# MiniRover.net
KiCad netlist of a schematic drawn in Altium Designer
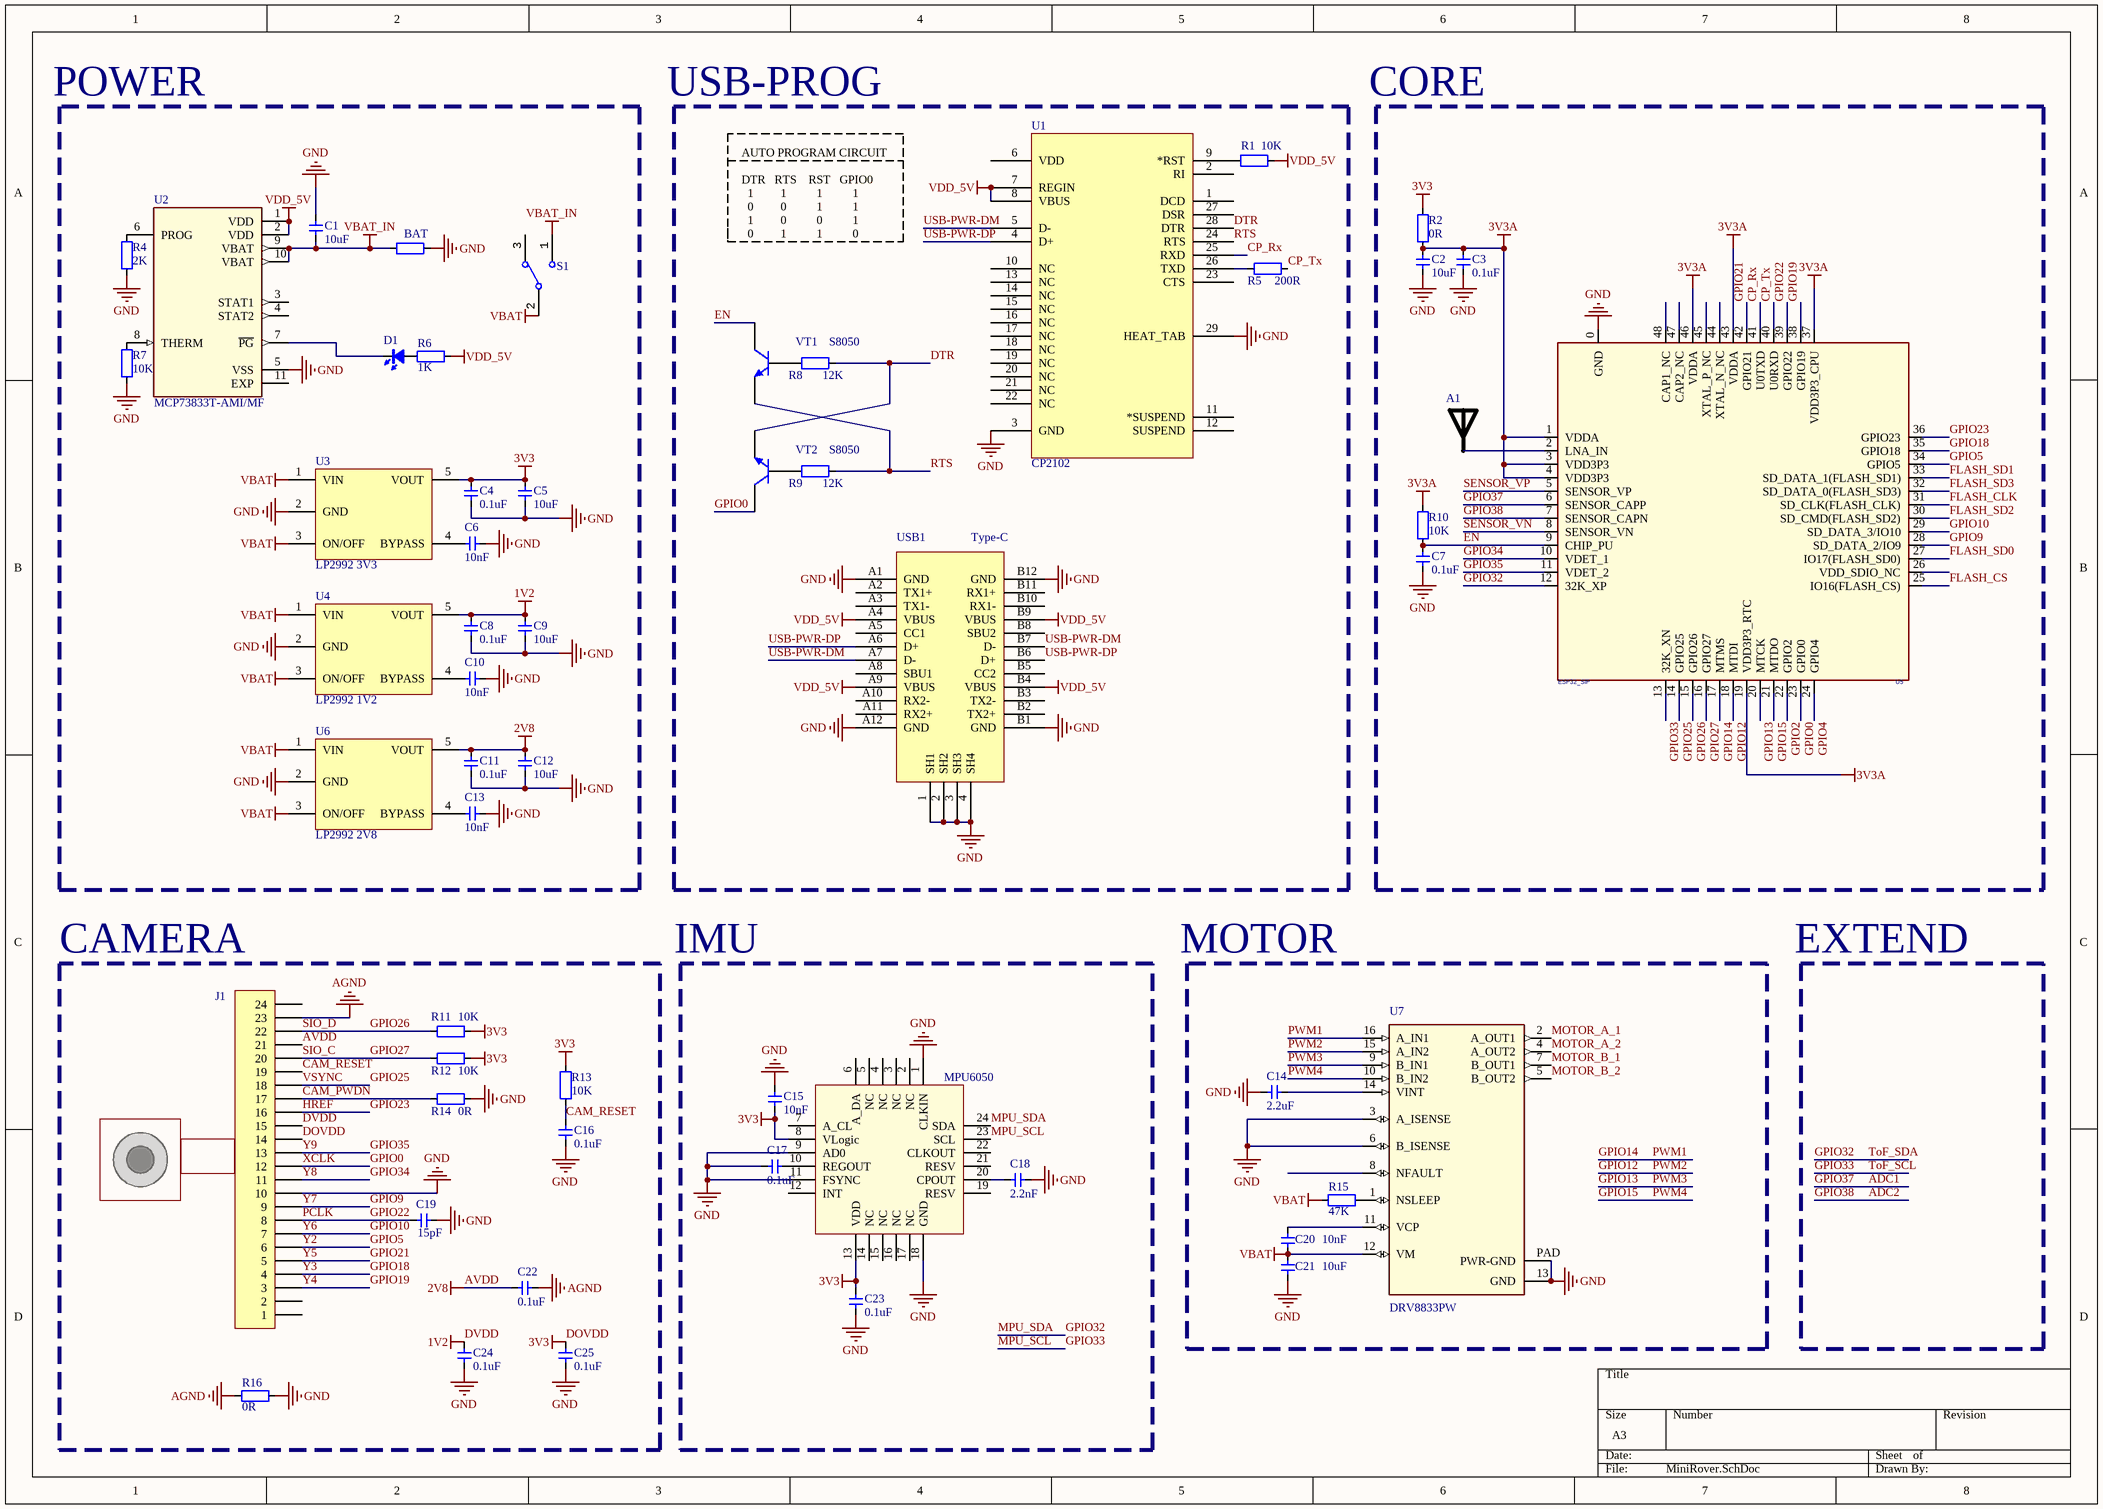
[diagram p0: MiniRover.SchDoc]

(export (version "E")
  (design (tool "Eeschema 10.0.6"))
  (components
    (comp (ref "A1")
      (value "RAINSUN")
      (footprint "ANT-Rainsun-AN5120")
      (libsource (lib "MyPcbLib") (part "ANT-Rainsun-AP5120"))
    )
    (comp (ref "C1")
      (value "10uF")
      (footprint "0603-CAP")
      (description "Capacitor")
      (libsource (lib "MyPcbLib") (part "电容-0603"))
    )
    (comp (ref "C2")
      (value "10uF")
      (footprint "0603-CAP")
      (description "Capacitor")
      (libsource (lib "MyPcbLib") (part "电容-0603"))
    )
    (comp (ref "C3")
      (value "0.1uF")
      (footprint "CAP_0402")
      (description "Capacitor")
      (libsource (lib "MyPcbLib") (part "电容-0402"))
    )
    (comp (ref "C4")
      (value "0.1uF")
      (footprint "CAP_0402")
      (description "Capacitor")
      (libsource (lib "MyPcbLib") (part "电容-0402"))
    )
    (comp (ref "C5")
      (value "10uF")
      (footprint "0603-CAP")
      (description "Capacitor")
      (libsource (lib "MyPcbLib") (part "电容-0603"))
    )
    (comp (ref "C6")
      (value "10nF")
      (footprint "CAP_0402")
      (description "Capacitor")
      (libsource (lib "MyPcbLib") (part "电容-0402"))
    )
    (comp (ref "C7")
      (value "0.1uF")
      (footprint "CAP_0402")
      (description "Capacitor")
      (libsource (lib "MyPcbLib") (part "电容-0402"))
    )
    (comp (ref "C8")
      (value "0.1uF")
      (footprint "CAP_0402")
      (description "Capacitor")
      (libsource (lib "MyPcbLib") (part "电容-0402"))
    )
    (comp (ref "C9")
      (value "10uF")
      (footprint "0603-CAP")
      (description "Capacitor")
      (libsource (lib "MyPcbLib") (part "电容-0603"))
    )
    (comp (ref "C10")
      (value "10nF")
      (footprint "CAP_0402")
      (description "Capacitor")
      (libsource (lib "MyPcbLib") (part "电容-0402"))
    )
    (comp (ref "C11")
      (value "0.1uF")
      (footprint "CAP_0402")
      (description "Capacitor")
      (libsource (lib "MyPcbLib") (part "电容-0402"))
    )
    (comp (ref "C12")
      (value "10uF")
      (footprint "0603-CAP")
      (description "Capacitor")
      (libsource (lib "MyPcbLib") (part "电容-0603"))
    )
    (comp (ref "C13")
      (value "10nF")
      (footprint "CAP_0402")
      (description "Capacitor")
      (libsource (lib "MyPcbLib") (part "电容-0402"))
    )
    (comp (ref "C14")
      (value "2.2uF")
      (footprint "CAP_0402")
      (description "Capacitor")
      (libsource (lib "MyPcbLib") (part "电容-0402"))
    )
    (comp (ref "C15")
      (value "10nF")
      (footprint "CAP_0402")
      (description "Capacitor")
      (libsource (lib "MyPcbLib") (part "电容-0402"))
    )
    (comp (ref "C16")
      (value "0.1uF")
      (footprint "CAP_0402")
      (description "Capacitor")
      (libsource (lib "MyPcbLib") (part "电容-0402"))
    )
    (comp (ref "C17")
      (value "0.1uF")
      (footprint "CAP_0402")
      (description "Capacitor")
      (libsource (lib "MyPcbLib") (part "电容-0402"))
    )
    (comp (ref "C18")
      (value "2.2nF")
      (footprint "CAP_0402")
      (description "Capacitor")
      (libsource (lib "MyPcbLib") (part "电容-0402"))
    )
    (comp (ref "C19")
      (value "15pF")
      (footprint "CAP_0402")
      (description "Capacitor")
      (libsource (lib "MyPcbLib") (part "电容-0402"))
    )
    (comp (ref "C20")
      (value "10nF")
      (footprint "CAP_0402")
      (description "Capacitor")
      (libsource (lib "MyPcbLib") (part "电容-0402"))
    )
    (comp (ref "C21")
      (value "10uF")
      (footprint "CAP_0402")
      (description "Capacitor")
      (libsource (lib "MyPcbLib") (part "电容-0402"))
    )
    (comp (ref "C22")
      (value "0.1uF")
      (footprint "CAP_0402")
      (description "Capacitor")
      (libsource (lib "MyPcbLib") (part "电容-0402"))
    )
    (comp (ref "C23")
      (value "0.1uF")
      (footprint "CAP_0402")
      (description "Capacitor")
      (libsource (lib "MyPcbLib") (part "电容-0402"))
    )
    (comp (ref "C24")
      (value "0.1uF")
      (footprint "CAP_0402")
      (description "Capacitor")
      (libsource (lib "MyPcbLib") (part "电容-0402"))
    )
    (comp (ref "C25")
      (value "0.1uF")
      (footprint "CAP_0402")
      (description "Capacitor")
      (libsource (lib "MyPcbLib") (part "电容-0402"))
    )
    (comp (ref "D1")
      (value "color?")
      (footprint "LED_0402_RED")
      (description "LED")
      (libsource (lib "KitSprout") (part "LED_0402"))
    )
    (comp (ref "J1")
      (value "0.5S_A_24PWB")
      (footprint "FPC-24P")
      (description "Header, 24-Pin")
      (fields (field (name "PUBLISHER") "Altium Limited"))
      (libsource (lib "MyPcbLib") (part "OV2640"))
    )
    (comp (ref "R1")
      (value "10K")
      (footprint "RES_0402")
      (description "Resistor")
      (libsource (lib "MyPcbLib") (part "电阻-0402"))
    )
    (comp (ref "R2")
      (value "0R")
      (footprint "RES_0402")
      (description "Resistor")
      (libsource (lib "") (part "电阻-0402_2"))
    )
    (comp (ref "R3")
      (value "BAT")
      (footprint "0805-L")
      (description "Resistor")
      (libsource (lib "MyPcbLib") (part "电阻-0805"))
    )
    (comp (ref "R4")
      (value "2K")
      (footprint "RES_0402")
      (description "Resistor")
      (libsource (lib "") (part "电阻-0402_1"))
    )
    (comp (ref "R5")
      (value "200R")
      (footprint "RES_0402")
      (description "Resistor")
      (libsource (lib "MyPcbLib") (part "电阻-0402"))
    )
    (comp (ref "R6")
      (value "1K")
      (footprint "RES_0402")
      (description "Resistor")
      (libsource (lib "MyPcbLib") (part "电阻-0402"))
    )
    (comp (ref "R7")
      (value "10K")
      (footprint "RES_0402")
      (description "Resistor")
      (libsource (lib "") (part "电阻-0402_1"))
    )
    (comp (ref "R8")
      (value "12K")
      (footprint "RES_0402")
      (description "Resistor")
      (libsource (lib "MyPcbLib") (part "电阻-0402"))
    )
    (comp (ref "R9")
      (value "12K")
      (footprint "RES_0402")
      (description "Resistor")
      (libsource (lib "MyPcbLib") (part "电阻-0402"))
    )
    (comp (ref "R10")
      (value "10K")
      (footprint "RES_0402")
      (description "Resistor")
      (libsource (lib "") (part "电阻-0402_2"))
    )
    (comp (ref "R11")
      (value "10K")
      (footprint "RES_0402")
      (description "Resistor")
      (libsource (lib "") (part "电阻-0402_3"))
    )
    (comp (ref "R12")
      (value "10K")
      (footprint "RES_0402")
      (description "Resistor")
      (libsource (lib "") (part "电阻-0402_3"))
    )
    (comp (ref "R13")
      (value "10K")
      (footprint "RES_0402")
      (description "Resistor")
      (libsource (lib "") (part "电阻-0402_1"))
    )
    (comp (ref "R14")
      (value "0R")
      (footprint "RES_0402")
      (description "Resistor")
      (libsource (lib "") (part "电阻-0402_3"))
    )
    (comp (ref "R15")
      (value "47K")
      (footprint "RES_0402")
      (description "Resistor")
      (libsource (lib "MyPcbLib") (part "电阻-0402"))
    )
    (comp (ref "R16")
      (value "0R")
      (footprint "RES_0402")
      (description "Resistor")
      (libsource (lib "") (part "电阻-0402_3"))
    )
    (comp (ref "S1")
      (value "SPDT 3P")
      (footprint "SwitchSPDT_2.8X6.6_90")
      (description "Switch")
      (libsource (lib "KitSprout") (part "SwitchSPDT_2.8x6.6_90"))
    )
    (comp (ref "U1")
      (value "CP2102")
      (footprint "QFN-28")
      (description "USB转TTL")
      (libsource (lib "mLib") (part "CP2102"))
    )
    (comp (ref "U2")
      (value "MCP73833T-AMI/MF")
      (footprint "QFN-10")
      (description "Linear Charge Management Controller Li-Ion/Li-Pol 1mA 4.2V/4.35V/4.4V/4.5V 10-Pin DFN EP T/R")
      (fields (field (name "MF") "Microchip"))
      (libsource (lib "mLib") (part "MCP73833T"))
    )
    (comp (ref "U3")
      (value "LP2992 3V3")
      (footprint "SOT23-5")
      (description "LDO")
      (libsource (lib "MyPcbLib") (part "LP2992"))
    )
    (comp (ref "U4")
      (value "LP2992 1V2")
      (footprint "SOT23-5")
      (description "LDO")
      (libsource (lib "MyPcbLib") (part "LP2992"))
    )
    (comp (ref "U5")
      (value "ESP32_SIP")
      (footprint "QFN-48_7X7")
      (libsource (lib "MyPcbLib") (part "ESP32-PICO"))
    )
    (comp (ref "U6")
      (value "LP2992 2V8")
      (footprint "SOT23-5")
      (description "LDO")
      (libsource (lib "MyPcbLib") (part "LP2992"))
    )
    (comp (ref "U7") (value "DRV8833PW") (footprint "TSSOP-16") (libsource (lib "mLib") (part "DRV8833PW")))
    (comp (ref "U8")
      (value "MPU6050")
      (footprint "QFN-24")
      (description "六轴传感器")
      (libsource (lib "mLib") (part "MPU6050"))
    )
    (comp (ref "USB1")
      (value "Type-C")
      (footprint "Type-C-TOP")
      (libsource (lib "MyPcbLib") (part "USB-Type-C-TOP"))
    )
    (comp (ref "VT1")
      (value "S8050")
      (footprint "SMT_TRIODE_NPN")
      (description "Surface mount NPN transistor, package SOT-23")
      (libsource (lib "MyPcbLib") (part "SMT_TRIODE_NPN"))
    )
    (comp (ref "VT2")
      (value "S8050")
      (footprint "SMT_TRIODE_NPN")
      (description "Surface mount NPN transistor, package SOT-23")
      (libsource (lib "MyPcbLib") (part "SMT_TRIODE_NPN"))
    )
  )
  (nets
    (net (code "1") (name "/ADC1") (class "Default")
      (node (ref "U5") (pin "6") (pinfunction "SENSOR_CAPP_6") (pintype "passive"))
    )
    (net (code "2") (name "/ADC2") (class "Default")
      (node (ref "U5") (pin "7") (pinfunction "SENSOR_CAPN_7") (pintype "passive"))
    )
    (net (code "3") (name "/CAM_PWDN") (class "Default")
      (node (ref "J1") (pin "17") (pinfunction "17_17") (pintype "passive"))
      (node (ref "R14") (pin "1") (pinfunction "1_1") (pintype "passive"))
    )
    (net (code "4") (name "/CAM_RESET") (class "Default")
      (node (ref "C16") (pin "2") (pinfunction "2_2") (pintype "passive"))
      (node (ref "J1") (pin "19") (pinfunction "19_19") (pintype "passive"))
      (node (ref "R13") (pin "1") (pinfunction "1_1") (pintype "passive"))
    )
    (net (code "5") (name "/CP_Rx") (class "Default")
      (node (ref "U1") (pin "25") (pinfunction "RXD_25") (pintype "passive"))
      (node (ref "U5") (pin "41") (pinfunction "U0TXD_41") (pintype "power_in"))
    )
    (net (code "6") (name "/CP_Tx") (class "Default")
      (node (ref "R5") (pin "1") (pinfunction "1_1") (pintype "passive"))
      (node (ref "U5") (pin "40") (pinfunction "U0RXD_40") (pintype "power_in"))
    )
    (net (code "7") (name "/DTR") (class "Default")
      (node (ref "R8") (pin "1") (pinfunction "1_1") (pintype "passive"))
      (node (ref "U1") (pin "28") (pinfunction "DTR_28") (pintype "passive"))
      (node (ref "VT2") (pin "2") (pinfunction "E_2") (pintype "passive"))
    )
    (net (code "8") (name "/EN") (class "Default")
      (node (ref "C7") (pin "1") (pinfunction "1_1") (pintype "passive"))
      (node (ref "R10") (pin "2") (pinfunction "2_2") (pintype "passive"))
      (node (ref "U5") (pin "9") (pinfunction "CHIP_PU_9") (pintype "passive"))
      (node (ref "VT1") (pin "3") (pinfunction "C_3") (pintype "passive"))
    )
    (net (code "9") (name "/FLASH_CLK") (class "Default")
      (node (ref "U5") (pin "31") (pinfunction "SD_CLK(FLASH_CLK)_31") (pintype "passive"))
    )
    (net (code "10") (name "/FLASH_CS") (class "Default")
      (node (ref "U5") (pin "25") (pinfunction "IO16(FLASH_CS)_25") (pintype "passive"))
    )
    (net (code "11") (name "/FLASH_SD0") (class "Default")
      (node (ref "U5") (pin "27") (pinfunction "IO17(FLASH_SD0)_27") (pintype "passive"))
    )
    (net (code "12") (name "/FLASH_SD1") (class "Default")
      (node (ref "U5") (pin "33") (pinfunction "SD_DATA_1(FLASH_SD1)_33") (pintype "passive"))
    )
    (net (code "13") (name "/FLASH_SD2") (class "Default")
      (node (ref "U5") (pin "30") (pinfunction "SD_CMD(FLASH_SD2)_30") (pintype "passive"))
    )
    (net (code "14") (name "/FLASH_SD3") (class "Default")
      (node (ref "U5") (pin "32") (pinfunction "SD_DATA_0(FLASH_SD3)_32") (pintype "passive"))
    )
    (net (code "15") (name "/GPIO0") (class "Default")
      (node (ref "J1") (pin "12") (pinfunction "12_12") (pintype "passive"))
      (node (ref "U5") (pin "23") (pinfunction "GPIO0_23") (pintype "passive"))
      (node (ref "VT2") (pin "3") (pinfunction "C_3") (pintype "passive"))
    )
    (net (code "16") (name "/GPIO2") (class "Default")
      (node (ref "U5") (pin "22") (pinfunction "GPIO2_22") (pintype "passive"))
    )
    (net (code "17") (name "/GPIO4") (class "Default")
      (node (ref "U5") (pin "24") (pinfunction "GPIO4_24") (pintype "passive"))
    )
    (net (code "18") (name "/GPIO5") (class "Default")
      (node (ref "J1") (pin "6") (pinfunction "6_6") (pintype "passive"))
      (node (ref "U5") (pin "34") (pinfunction "GPIO5_34") (pintype "passive"))
    )
    (net (code "19") (name "/GPIO9") (class "Default")
      (node (ref "J1") (pin "9") (pinfunction "9_9") (pintype "passive"))
      (node (ref "U5") (pin "28") (pinfunction "SD_DATA_2/IO9_28") (pintype "passive"))
    )
    (net (code "20") (name "/GPIO10") (class "Default")
      (node (ref "J1") (pin "7") (pinfunction "7_7") (pintype "passive"))
      (node (ref "U5") (pin "29") (pinfunction "SD_DATA_3/IO10_29") (pintype "passive"))
    )
    (net (code "21") (name "/GPIO12") (class "Default")
      (node (ref "U5") (pin "18") (pinfunction "MTDI_18") (pintype "passive"))
      (node (ref "U7") (pin "15") (pinfunction "A_IN2_15") (pintype "input"))
    )
    (net (code "22") (name "/GPIO13") (class "Default")
      (node (ref "U5") (pin "20") (pinfunction "MTCK_20") (pintype "passive"))
      (node (ref "U7") (pin "9") (pinfunction "B_IN1_9") (pintype "input"))
    )
    (net (code "23") (name "/GPIO14") (class "Default")
      (node (ref "U5") (pin "17") (pinfunction "MTMS_17") (pintype "passive"))
      (node (ref "U7") (pin "16") (pinfunction "A_IN1_16") (pintype "input"))
    )
    (net (code "24") (name "/GPIO15") (class "Default")
      (node (ref "U5") (pin "21") (pinfunction "MTDO_21") (pintype "passive"))
      (node (ref "U7") (pin "10") (pinfunction "B_IN2_10") (pintype "input"))
    )
    (net (code "25") (name "/GPIO18") (class "Default")
      (node (ref "J1") (pin "4") (pinfunction "4_4") (pintype "passive"))
      (node (ref "U5") (pin "35") (pinfunction "GPIO18_35") (pintype "passive"))
    )
    (net (code "26") (name "/GPIO19") (class "Default")
      (node (ref "J1") (pin "3") (pinfunction "3_3") (pintype "passive"))
      (node (ref "U5") (pin "38") (pinfunction "GPIO19_38") (pintype "passive"))
    )
    (net (code "27") (name "/GPIO21") (class "Default")
      (node (ref "J1") (pin "5") (pinfunction "5_5") (pintype "passive"))
      (node (ref "U5") (pin "42") (pinfunction "GPIO21_42") (pintype "passive"))
    )
    (net (code "28") (name "/GPIO22") (class "Default")
      (node (ref "C19") (pin "1") (pinfunction "1_1") (pintype "passive"))
      (node (ref "J1") (pin "8") (pinfunction "8_8") (pintype "passive"))
      (node (ref "U5") (pin "39") (pinfunction "GPIO22_39") (pintype "passive"))
    )
    (net (code "29") (name "/GPIO23") (class "Default")
      (node (ref "J1") (pin "16") (pinfunction "16_16") (pintype "passive"))
      (node (ref "U5") (pin "36") (pinfunction "GPIO23_36") (pintype "passive"))
    )
    (net (code "30") (name "/GPIO25") (class "Default")
      (node (ref "J1") (pin "18") (pinfunction "18_18") (pintype "passive"))
      (node (ref "U5") (pin "14") (pinfunction "GPIO25_14") (pintype "passive"))
    )
    (net (code "31") (name "/GPIO26") (class "Default")
      (node (ref "J1") (pin "22") (pinfunction "22_22") (pintype "passive"))
      (node (ref "R11") (pin "1") (pinfunction "1_1") (pintype "passive"))
      (node (ref "U5") (pin "15") (pinfunction "GPIO26_15") (pintype "passive"))
    )
    (net (code "32") (name "/GPIO27") (class "Default")
      (node (ref "J1") (pin "20") (pinfunction "20_20") (pintype "passive"))
      (node (ref "R12") (pin "1") (pinfunction "1_1") (pintype "passive"))
      (node (ref "U5") (pin "16") (pinfunction "GPIO27_16") (pintype "passive"))
    )
    (net (code "33") (name "/GPIO32") (class "Default")
      (node (ref "U5") (pin "12") (pinfunction "32K_XP_12") (pintype "passive"))
      (node (ref "U8") (pin "24") (pinfunction "SDA_24") (pintype "passive"))
    )
    (net (code "34") (name "/GPIO33") (class "Default")
      (node (ref "U5") (pin "13") (pinfunction "32K_XN_13") (pintype "passive"))
      (node (ref "U8") (pin "23") (pinfunction "SCL_23") (pintype "passive"))
    )
    (net (code "35") (name "/GPIO34") (class "Default")
      (node (ref "J1") (pin "11") (pinfunction "11_11") (pintype "passive"))
      (node (ref "U5") (pin "10") (pinfunction "VDET_1_10") (pintype "passive"))
    )
    (net (code "36") (name "/GPIO35") (class "Default")
      (node (ref "J1") (pin "13") (pinfunction "13_13") (pintype "passive"))
      (node (ref "U5") (pin "11") (pinfunction "VDET_2_11") (pintype "passive"))
    )
    (net (code "37") (name "/MOTOR_A_1") (class "Default")
      (node (ref "U7") (pin "2") (pinfunction "A_OUT1_2") (pintype "output"))
    )
    (net (code "38") (name "/MOTOR_A_2") (class "Default")
      (node (ref "U7") (pin "4") (pinfunction "A_OUT2_4") (pintype "output"))
    )
    (net (code "39") (name "/MOTOR_B_1") (class "Default")
      (node (ref "U7") (pin "7") (pinfunction "B_OUT1_7") (pintype "output"))
    )
    (net (code "40") (name "/MOTOR_B_2") (class "Default")
      (node (ref "U7") (pin "5") (pinfunction "B_OUT2_5") (pintype "output"))
    )
    (net (code "41") (name "/RTS") (class "Default")
      (node (ref "R9") (pin "1") (pinfunction "1_1") (pintype "passive"))
      (node (ref "U1") (pin "24") (pinfunction "RTS_24") (pintype "passive"))
      (node (ref "VT1") (pin "2") (pinfunction "E_2") (pintype "passive"))
    )
    (net (code "42") (name "/SENSOR_VN") (class "Default")
      (node (ref "U5") (pin "8") (pinfunction "SENSOR_VN_8") (pintype "passive"))
    )
    (net (code "43") (name "/SENSOR_VP") (class "Default")
      (node (ref "U5") (pin "5") (pinfunction "SENSOR_VP_5") (pintype "passive"))
    )
    (net (code "44") (name "/USB-PWR-DM") (class "Default")
      (node (ref "U1") (pin "5") (pinfunction "D-_5") (pintype "passive"))
      (node (ref "USB1") (pin "A7") (pinfunction "D-_A7") (pintype "passive"))
      (node (ref "USB1") (pin "B7") (pinfunction "D-_B7") (pintype "passive"))
    )
    (net (code "45") (name "/USB-PWR-DP") (class "Default")
      (node (ref "U1") (pin "4") (pinfunction "D+_4") (pintype "passive"))
      (node (ref "USB1") (pin "A6") (pinfunction "D+_A6") (pintype "passive"))
      (node (ref "USB1") (pin "B6") (pinfunction "D+_B6") (pintype "passive"))
    )
    (net (code "46") (name "1V2") (class "Default")
      (node (ref "C24") (pin "2") (pinfunction "2_2") (pintype "passive"))
      (node (ref "C8") (pin "2") (pinfunction "2_2") (pintype "passive"))
      (node (ref "C9") (pin "2") (pinfunction "2_2") (pintype "passive"))
      (node (ref "J1") (pin "15") (pinfunction "15_15") (pintype "passive"))
      (node (ref "U4") (pin "5") (pinfunction "VOUT_5") (pintype "passive"))
    )
    (net (code "47") (name "2V8") (class "Default")
      (node (ref "C11") (pin "2") (pinfunction "2_2") (pintype "passive"))
      (node (ref "C12") (pin "2") (pinfunction "2_2") (pintype "passive"))
      (node (ref "C22") (pin "2") (pinfunction "2_2") (pintype "passive"))
      (node (ref "J1") (pin "21") (pinfunction "21_21") (pintype "passive"))
      (node (ref "U6") (pin "5") (pinfunction "VOUT_5") (pintype "passive"))
    )
    (net (code "48") (name "3V3") (class "Default")
      (node (ref "C15") (pin "1") (pinfunction "1_1") (pintype "passive"))
      (node (ref "C23") (pin "2") (pinfunction "2_2") (pintype "passive"))
      (node (ref "C25") (pin "2") (pinfunction "2_2") (pintype "passive"))
      (node (ref "C4") (pin "2") (pinfunction "2_2") (pintype "passive"))
      (node (ref "C5") (pin "2") (pinfunction "2_2") (pintype "passive"))
      (node (ref "J1") (pin "14") (pinfunction "14_14") (pintype "passive"))
      (node (ref "R11") (pin "2") (pinfunction "2_2") (pintype "passive"))
      (node (ref "R12") (pin "2") (pinfunction "2_2") (pintype "passive"))
      (node (ref "R13") (pin "2") (pinfunction "2_2") (pintype "passive"))
      (node (ref "R2") (pin "1") (pinfunction "1_1") (pintype "passive"))
      (node (ref "U3") (pin "5") (pinfunction "VOUT_5") (pintype "passive"))
      (node (ref "U8") (pin "13") (pinfunction "VDD_13") (pintype "passive"))
      (node (ref "U8") (pin "8") (pinfunction "VLogic_8") (pintype "passive"))
    )
    (net (code "49") (name "3V3A") (class "Default")
      (node (ref "C2") (pin "2") (pinfunction "2_2") (pintype "passive"))
      (node (ref "C3") (pin "2") (pinfunction "2_2") (pintype "passive"))
      (node (ref "R10") (pin "1") (pinfunction "1_1") (pintype "passive"))
      (node (ref "R2") (pin "2") (pinfunction "2_2") (pintype "passive"))
      (node (ref "U5") (pin "1") (pinfunction "VDDA_1") (pintype "power_in"))
      (node (ref "U5") (pin "19") (pinfunction "VDD3P3_RTC_19") (pintype "power_in"))
      (node (ref "U5") (pin "3") (pinfunction "VDD3P3_3") (pintype "power_in"))
      (node (ref "U5") (pin "37") (pinfunction "VDD3P3_CPU_37") (pintype "power_in"))
      (node (ref "U5") (pin "4") (pinfunction "VDD3P3_4") (pintype "power_in"))
      (node (ref "U5") (pin "43") (pinfunction "VDDA_43") (pintype "power_in"))
      (node (ref "U5") (pin "46") (pinfunction "VDDA_46") (pintype "power_in"))
    )
    (net (code "50") (name "AGND") (class "Default")
      (node (ref "C22") (pin "1") (pinfunction "1_1") (pintype "passive"))
      (node (ref "J1") (pin "23") (pinfunction "23_23") (pintype "passive"))
      (node (ref "R16") (pin "1") (pinfunction "1_1") (pintype "passive"))
    )
    (net (code "51") (name "GND") (class "Default")
      (node (ref "C1") (pin "2") (pinfunction "2_2") (pintype "passive"))
      (node (ref "C10") (pin "1") (pinfunction "1_1") (pintype "passive"))
      (node (ref "C11") (pin "1") (pinfunction "1_1") (pintype "passive"))
      (node (ref "C12") (pin "1") (pinfunction "1_1") (pintype "passive"))
      (node (ref "C13") (pin "1") (pinfunction "1_1") (pintype "passive"))
      (node (ref "C14") (pin "1") (pinfunction "1_1") (pintype "passive"))
      (node (ref "C15") (pin "2") (pinfunction "2_2") (pintype "passive"))
      (node (ref "C16") (pin "1") (pinfunction "1_1") (pintype "passive"))
      (node (ref "C17") (pin "2") (pinfunction "2_2") (pintype "passive"))
      (node (ref "C18") (pin "1") (pinfunction "1_1") (pintype "passive"))
      (node (ref "C19") (pin "2") (pinfunction "2_2") (pintype "passive"))
      (node (ref "C2") (pin "1") (pinfunction "1_1") (pintype "passive"))
      (node (ref "C21") (pin "1") (pinfunction "1_1") (pintype "passive"))
      (node (ref "C23") (pin "1") (pinfunction "1_1") (pintype "passive"))
      (node (ref "C24") (pin "1") (pinfunction "1_1") (pintype "passive"))
      (node (ref "C25") (pin "1") (pinfunction "1_1") (pintype "passive"))
      (node (ref "C3") (pin "1") (pinfunction "1_1") (pintype "passive"))
      (node (ref "C4") (pin "1") (pinfunction "1_1") (pintype "passive"))
      (node (ref "C5") (pin "1") (pinfunction "1_1") (pintype "passive"))
      (node (ref "C6") (pin "1") (pinfunction "1_1") (pintype "passive"))
      (node (ref "C7") (pin "2") (pinfunction "2_2") (pintype "passive"))
      (node (ref "C8") (pin "1") (pinfunction "1_1") (pintype "passive"))
      (node (ref "C9") (pin "1") (pinfunction "1_1") (pintype "passive"))
      (node (ref "J1") (pin "10") (pinfunction "10_10") (pintype "passive"))
      (node (ref "R14") (pin "2") (pinfunction "2_2") (pintype "passive"))
      (node (ref "R16") (pin "2") (pinfunction "2_2") (pintype "passive"))
      (node (ref "R3") (pin "2") (pinfunction "2_2") (pintype "passive"))
      (node (ref "R4") (pin "1") (pinfunction "1_1") (pintype "passive"))
      (node (ref "R7") (pin "1") (pinfunction "1_1") (pintype "passive"))
      (node (ref "U1") (pin "29") (pinfunction "HEAT_TAB_29") (pintype "passive"))
      (node (ref "U1") (pin "3") (pinfunction "GND_3") (pintype "passive"))
      (node (ref "U2") (pin "5") (pinfunction "VSS_5") (pintype "power_in"))
      (node (ref "U3") (pin "2") (pinfunction "GND_2") (pintype "passive"))
      (node (ref "U4") (pin "2") (pinfunction "GND_2") (pintype "passive"))
      (node (ref "U5") (pin "0") (pinfunction "GND_0") (pintype "power_in"))
      (node (ref "U6") (pin "2") (pinfunction "GND_2") (pintype "passive"))
      (node (ref "U7") (pin "13") (pinfunction "GND_13") (pintype "power_in"))
      (node (ref "U7") (pin "3") (pinfunction "A_ISENSE_3") (pintype "bidirectional"))
      (node (ref "U7") (pin "6") (pinfunction "B_ISENSE_6") (pintype "bidirectional"))
      (node (ref "U7") (pin "PAD") (pinfunction "PWR-GND_PAD") (pintype "power_in"))
      (node (ref "U8") (pin "1") (pinfunction "CLKIN_1") (pintype "passive"))
      (node (ref "U8") (pin "11") (pinfunction "FSYNC_11") (pintype "passive"))
      (node (ref "U8") (pin "18") (pinfunction "GND_18") (pintype "passive"))
      (node (ref "U8") (pin "9") (pinfunction "AD0_9") (pintype "passive"))
      (node (ref "USB1") (pin "1") (pinfunction "SH1_1") (pintype "passive"))
      (node (ref "USB1") (pin "2") (pinfunction "SH2_2") (pintype "passive"))
      (node (ref "USB1") (pin "3") (pinfunction "SH3_3") (pintype "passive"))
      (node (ref "USB1") (pin "4") (pinfunction "SH4_4") (pintype "passive"))
      (node (ref "USB1") (pin "A1") (pinfunction "GND_A1") (pintype "passive"))
      (node (ref "USB1") (pin "A12") (pinfunction "GND_A12") (pintype "passive"))
      (node (ref "USB1") (pin "B1") (pinfunction "GND_B1") (pintype "passive"))
      (node (ref "USB1") (pin "B12") (pinfunction "GND_B12") (pintype "passive"))
    )
    (net (code "52") (name "Net-(D1-A)") (class "Default")
      (node (ref "D1") (pin "1") (pinfunction "A_1") (pintype "passive"))
      (node (ref "R6") (pin "2") (pinfunction "2_2") (pintype "passive"))
    )
    (net (code "53") (name "Net-(D1-K)") (class "Default")
      (node (ref "D1") (pin "2") (pinfunction "K_2") (pintype "passive"))
      (node (ref "U2") (pin "7") (pinfunction "~{PG}_7") (pintype "output"))
    )
    (net (code "54") (name "Net-(U1-*RST)") (class "Default")
      (node (ref "R1") (pin "2") (pinfunction "2_2") (pintype "passive"))
      (node (ref "U1") (pin "9") (pinfunction "*RST_9") (pintype "passive"))
    )
    (net (code "55") (name "Net-(U1-TXD)") (class "Default")
      (node (ref "R5") (pin "2") (pinfunction "2_2") (pintype "passive"))
      (node (ref "U1") (pin "26") (pinfunction "TXD_26") (pintype "passive"))
    )
    (net (code "56") (name "Net-(U2-PROG)") (class "Default")
      (node (ref "R4") (pin "2") (pinfunction "2_2") (pintype "passive"))
      (node (ref "U2") (pin "6") (pinfunction "PROG_6") (pintype "passive"))
    )
    (net (code "57") (name "Net-(U2-THERM)") (class "Default")
      (node (ref "R7") (pin "2") (pinfunction "2_2") (pintype "passive"))
      (node (ref "U2") (pin "8") (pinfunction "THERM_8") (pintype "input"))
    )
    (net (code "58") (name "Net-(U3-BYPASS)") (class "Default")
      (node (ref "C6") (pin "2") (pinfunction "2_2") (pintype "passive"))
      (node (ref "U3") (pin "4") (pinfunction "BYPASS_4") (pintype "passive"))
    )
    (net (code "59") (name "Net-(U4-BYPASS)") (class "Default")
      (node (ref "C10") (pin "2") (pinfunction "2_2") (pintype "passive"))
      (node (ref "U4") (pin "4") (pinfunction "BYPASS_4") (pintype "passive"))
    )
    (net (code "60") (name "Net-(U5-LNA_IN)") (class "Default")
      (node (ref "A1") (pin "1") (pinfunction "1_1") (pintype "passive"))
      (node (ref "U5") (pin "2") (pinfunction "LNA_IN_2") (pintype "passive"))
    )
    (net (code "61") (name "Net-(U6-BYPASS)") (class "Default")
      (node (ref "C13") (pin "2") (pinfunction "2_2") (pintype "passive"))
      (node (ref "U6") (pin "4") (pinfunction "BYPASS_4") (pintype "passive"))
    )
    (net (code "62") (name "Net-(U7-NSLEEP)") (class "Default")
      (node (ref "R15") (pin "1") (pinfunction "1_1") (pintype "passive"))
      (node (ref "U7") (pin "1") (pinfunction "NSLEEP_1") (pintype "bidirectional"))
    )
    (net (code "63") (name "Net-(U7-VCP)") (class "Default")
      (node (ref "C20") (pin "2") (pinfunction "2_2") (pintype "passive"))
      (node (ref "U7") (pin "11") (pinfunction "VCP_11") (pintype "bidirectional"))
    )
    (net (code "64") (name "Net-(U7-VINT)") (class "Default")
      (node (ref "C14") (pin "2") (pinfunction "2_2") (pintype "passive"))
      (node (ref "U7") (pin "14") (pinfunction "VINT_14") (pintype "input"))
    )
    (net (code "65") (name "Net-(U8-CPOUT)") (class "Default")
      (node (ref "C18") (pin "2") (pinfunction "2_2") (pintype "passive"))
      (node (ref "U8") (pin "20") (pinfunction "CPOUT_20") (pintype "passive"))
    )
    (net (code "66") (name "Net-(U8-REGOUT)") (class "Default")
      (node (ref "C17") (pin "1") (pinfunction "1_1") (pintype "passive"))
      (node (ref "U8") (pin "10") (pinfunction "REGOUT_10") (pintype "passive"))
    )
    (net (code "67") (name "Net-(VT1-B)") (class "Default")
      (node (ref "R8") (pin "2") (pinfunction "2_2") (pintype "passive"))
      (node (ref "VT1") (pin "1") (pinfunction "B_1") (pintype "passive"))
    )
    (net (code "68") (name "Net-(VT2-B)") (class "Default")
      (node (ref "R9") (pin "2") (pinfunction "2_2") (pintype "passive"))
      (node (ref "VT2") (pin "1") (pinfunction "B_1") (pintype "passive"))
    )
    (net (code "69") (name "VBAT") (class "Default")
      (node (ref "C20") (pin "1") (pinfunction "1_1") (pintype "passive"))
      (node (ref "C21") (pin "2") (pinfunction "2_2") (pintype "passive"))
      (node (ref "R15") (pin "2") (pinfunction "2_2") (pintype "passive"))
      (node (ref "S1") (pin "2") (pinfunction "2_2") (pintype "passive"))
      (node (ref "U3") (pin "1") (pinfunction "VIN_1") (pintype "passive"))
      (node (ref "U3") (pin "3") (pinfunction "ON/OFF_3") (pintype "passive"))
      (node (ref "U4") (pin "1") (pinfunction "VIN_1") (pintype "passive"))
      (node (ref "U4") (pin "3") (pinfunction "ON/OFF_3") (pintype "passive"))
      (node (ref "U6") (pin "1") (pinfunction "VIN_1") (pintype "passive"))
      (node (ref "U6") (pin "3") (pinfunction "ON/OFF_3") (pintype "passive"))
      (node (ref "U7") (pin "12") (pinfunction "VM_12") (pintype "bidirectional"))
    )
    (net (code "70") (name "VBAT_IN") (class "Default")
      (node (ref "C1") (pin "1") (pinfunction "1_1") (pintype "passive"))
      (node (ref "R3") (pin "1") (pinfunction "1_1") (pintype "passive"))
      (node (ref "S1") (pin "1") (pinfunction "1_1") (pintype "passive"))
      (node (ref "U2") (pin "10") (pinfunction "VBAT_10") (pintype "output"))
      (node (ref "U2") (pin "9") (pinfunction "VBAT_9") (pintype "output"))
    )
    (net (code "71") (name "VDD_5V") (class "Default")
      (node (ref "R1") (pin "1") (pinfunction "1_1") (pintype "passive"))
      (node (ref "R6") (pin "1") (pinfunction "1_1") (pintype "passive"))
      (node (ref "U1") (pin "7") (pinfunction "REGIN_7") (pintype "passive"))
      (node (ref "U1") (pin "8") (pinfunction "VBUS_8") (pintype "passive"))
      (node (ref "U2") (pin "1") (pinfunction "VDD_1") (pintype "power_in"))
      (node (ref "U2") (pin "2") (pinfunction "VDD_2") (pintype "power_in"))
      (node (ref "USB1") (pin "A4") (pinfunction "VBUS_A4") (pintype "passive"))
      (node (ref "USB1") (pin "A9") (pinfunction "VBUS_A9") (pintype "passive"))
      (node (ref "USB1") (pin "B4") (pinfunction "VBUS_B4") (pintype "passive"))
      (node (ref "USB1") (pin "B9") (pinfunction "VBUS_B9") (pintype "passive"))
    )
    (net (code "72") (name "unconnected-(J1-Pad1)") (class "Default")
      (node (ref "J1") (pin "1") (pinfunction "1_1") (pintype "passive"))
    )
    (net (code "73") (name "unconnected-(J1-Pad2)") (class "Default")
      (node (ref "J1") (pin "2") (pinfunction "2_2") (pintype "passive"))
    )
    (net (code "74") (name "unconnected-(J1-Pad24)") (class "Default")
      (node (ref "J1") (pin "24") (pinfunction "24_24") (pintype "passive"))
    )
    (net (code "75") (name "unconnected-(S1-Pad3)") (class "Default")
      (node (ref "S1") (pin "3") (pinfunction "3_3") (pintype "passive"))
    )
    (net (code "76") (name "unconnected-(U1-*SUSPEND-Pad11)") (class "Default")
      (node (ref "U1") (pin "11") (pinfunction "*SUSPEND_11") (pintype "passive"))
    )
    (net (code "77") (name "unconnected-(U1-CTS-Pad23)") (class "Default")
      (node (ref "U1") (pin "23") (pinfunction "CTS_23") (pintype "passive"))
    )
    (net (code "78") (name "unconnected-(U1-DCD-Pad1)") (class "Default")
      (node (ref "U1") (pin "1") (pinfunction "DCD_1") (pintype "passive"))
    )
    (net (code "79") (name "unconnected-(U1-DSR-Pad27)") (class "Default")
      (node (ref "U1") (pin "27") (pinfunction "DSR_27") (pintype "passive"))
    )
    (net (code "80") (name "unconnected-(U1-NC-Pad10)") (class "Default")
      (node (ref "U1") (pin "10") (pinfunction "NC_10") (pintype "passive"))
    )
    (net (code "81") (name "unconnected-(U1-NC-Pad13)") (class "Default")
      (node (ref "U1") (pin "13") (pinfunction "NC_13") (pintype "passive"))
    )
    (net (code "82") (name "unconnected-(U1-NC-Pad14)") (class "Default")
      (node (ref "U1") (pin "14") (pinfunction "NC_14") (pintype "passive"))
    )
    (net (code "83") (name "unconnected-(U1-NC-Pad15)") (class "Default")
      (node (ref "U1") (pin "15") (pinfunction "NC_15") (pintype "passive"))
    )
    (net (code "84") (name "unconnected-(U1-NC-Pad16)") (class "Default")
      (node (ref "U1") (pin "16") (pinfunction "NC_16") (pintype "passive"))
    )
    (net (code "85") (name "unconnected-(U1-NC-Pad17)") (class "Default")
      (node (ref "U1") (pin "17") (pinfunction "NC_17") (pintype "passive"))
    )
    (net (code "86") (name "unconnected-(U1-NC-Pad18)") (class "Default")
      (node (ref "U1") (pin "18") (pinfunction "NC_18") (pintype "passive"))
    )
    (net (code "87") (name "unconnected-(U1-NC-Pad19)") (class "Default")
      (node (ref "U1") (pin "19") (pinfunction "NC_19") (pintype "passive"))
    )
    (net (code "88") (name "unconnected-(U1-NC-Pad20)") (class "Default")
      (node (ref "U1") (pin "20") (pinfunction "NC_20") (pintype "passive"))
    )
    (net (code "89") (name "unconnected-(U1-NC-Pad21)") (class "Default")
      (node (ref "U1") (pin "21") (pinfunction "NC_21") (pintype "passive"))
    )
    (net (code "90") (name "unconnected-(U1-NC-Pad22)") (class "Default")
      (node (ref "U1") (pin "22") (pinfunction "NC_22") (pintype "passive"))
    )
    (net (code "91") (name "unconnected-(U1-RI-Pad2)") (class "Default")
      (node (ref "U1") (pin "2") (pinfunction "RI_2") (pintype "passive"))
    )
    (net (code "92") (name "unconnected-(U1-SUSPEND-Pad12)") (class "Default")
      (node (ref "U1") (pin "12") (pinfunction "SUSPEND_12") (pintype "passive"))
    )
    (net (code "93") (name "unconnected-(U1-VDD-Pad6)") (class "Default")
      (node (ref "U1") (pin "6") (pinfunction "VDD_6") (pintype "passive"))
    )
    (net (code "94") (name "unconnected-(U2-EXP-Pad11)") (class "Default")
      (node (ref "U2") (pin "11") (pinfunction "EXP_11") (pintype "passive"))
    )
    (net (code "95") (name "unconnected-(U2-STAT1-Pad3)") (class "Default")
      (node (ref "U2") (pin "3") (pinfunction "STAT1_3") (pintype "output"))
    )
    (net (code "96") (name "unconnected-(U2-STAT2-Pad4)") (class "Default")
      (node (ref "U2") (pin "4") (pinfunction "STAT2_4") (pintype "output"))
    )
    (net (code "97") (name "unconnected-(U5-CAP1_NC-Pad48)") (class "Default")
      (node (ref "U5") (pin "48") (pinfunction "CAP1_NC_48") (pintype "passive"))
    )
    (net (code "98") (name "unconnected-(U5-CAP2_NC-Pad47)") (class "Default")
      (node (ref "U5") (pin "47") (pinfunction "CAP2_NC_47") (pintype "passive"))
    )
    (net (code "99") (name "unconnected-(U5-VDD_SDIO_NC-Pad26)") (class "Default")
      (node (ref "U5") (pin "26") (pinfunction "VDD_SDIO_NC_26") (pintype "passive"))
    )
    (net (code "100") (name "unconnected-(U5-XTAL_N_NC-Pad44)") (class "Default")
      (node (ref "U5") (pin "44") (pinfunction "XTAL_N_NC_44") (pintype "passive"))
    )
    (net (code "101") (name "unconnected-(U5-XTAL_P_NC-Pad45)") (class "Default")
      (node (ref "U5") (pin "45") (pinfunction "XTAL_P_NC_45") (pintype "passive"))
    )
    (net (code "102") (name "unconnected-(U7-NFAULT-Pad8)") (class "Default")
      (node (ref "U7") (pin "8") (pinfunction "NFAULT_8") (pintype "bidirectional"))
    )
    (net (code "103") (name "unconnected-(U8-A_CL-Pad7)") (class "Default")
      (node (ref "U8") (pin "7") (pinfunction "A_CL_7") (pintype "passive"))
    )
    (net (code "104") (name "unconnected-(U8-A_DA-Pad6)") (class "Default")
      (node (ref "U8") (pin "6") (pinfunction "A_DA_6") (pintype "passive"))
    )
    (net (code "105") (name "unconnected-(U8-CLKOUT-Pad22)") (class "Default")
      (node (ref "U8") (pin "22") (pinfunction "CLKOUT_22") (pintype "passive"))
    )
    (net (code "106") (name "unconnected-(U8-INT-Pad12)") (class "Default")
      (node (ref "U8") (pin "12") (pinfunction "INT_12") (pintype "passive"))
    )
    (net (code "107") (name "unconnected-(U8-NC-Pad2)") (class "Default")
      (node (ref "U8") (pin "2") (pinfunction "NC_2") (pintype "passive"))
    )
    (net (code "108") (name "unconnected-(U8-NC-Pad3)") (class "Default")
      (node (ref "U8") (pin "3") (pinfunction "NC_3") (pintype "passive"))
    )
    (net (code "109") (name "unconnected-(U8-NC-Pad4)") (class "Default")
      (node (ref "U8") (pin "4") (pinfunction "NC_4") (pintype "passive"))
    )
    (net (code "110") (name "unconnected-(U8-NC-Pad5)") (class "Default")
      (node (ref "U8") (pin "5") (pinfunction "NC_5") (pintype "passive"))
    )
    (net (code "111") (name "unconnected-(U8-NC-Pad14)") (class "Default")
      (node (ref "U8") (pin "14") (pinfunction "NC_14") (pintype "passive"))
    )
    (net (code "112") (name "unconnected-(U8-NC-Pad15)") (class "Default")
      (node (ref "U8") (pin "15") (pinfunction "NC_15") (pintype "passive"))
    )
    (net (code "113") (name "unconnected-(U8-NC-Pad16)") (class "Default")
      (node (ref "U8") (pin "16") (pinfunction "NC_16") (pintype "passive"))
    )
    (net (code "114") (name "unconnected-(U8-NC-Pad17)") (class "Default")
      (node (ref "U8") (pin "17") (pinfunction "NC_17") (pintype "passive"))
    )
    (net (code "115") (name "unconnected-(U8-RESV-Pad19)") (class "Default")
      (node (ref "U8") (pin "19") (pinfunction "RESV_19") (pintype "passive"))
    )
    (net (code "116") (name "unconnected-(U8-RESV-Pad21)") (class "Default")
      (node (ref "U8") (pin "21") (pinfunction "RESV_21") (pintype "passive"))
    )
    (net (code "117") (name "unconnected-(USB1-CC1-PadA5)") (class "Default")
      (node (ref "USB1") (pin "A5") (pinfunction "CC1_A5") (pintype "passive"))
    )
    (net (code "118") (name "unconnected-(USB1-CC2-PadB5)") (class "Default")
      (node (ref "USB1") (pin "B5") (pinfunction "CC2_B5") (pintype "passive"))
    )
    (net (code "119") (name "unconnected-(USB1-RX1+-PadB11)") (class "Default")
      (node (ref "USB1") (pin "B11") (pinfunction "RX1+_B11") (pintype "passive"))
    )
    (net (code "120") (name "unconnected-(USB1-RX1--PadB10)") (class "Default")
      (node (ref "USB1") (pin "B10") (pinfunction "RX1-_B10") (pintype "passive"))
    )
    (net (code "121") (name "unconnected-(USB1-RX2+-PadA11)") (class "Default")
      (node (ref "USB1") (pin "A11") (pinfunction "RX2+_A11") (pintype "passive"))
    )
    (net (code "122") (name "unconnected-(USB1-RX2--PadA10)") (class "Default")
      (node (ref "USB1") (pin "A10") (pinfunction "RX2-_A10") (pintype "passive"))
    )
    (net (code "123") (name "unconnected-(USB1-SBU1-PadA8)") (class "Default")
      (node (ref "USB1") (pin "A8") (pinfunction "SBU1_A8") (pintype "passive"))
    )
    (net (code "124") (name "unconnected-(USB1-SBU2-PadB8)") (class "Default")
      (node (ref "USB1") (pin "B8") (pinfunction "SBU2_B8") (pintype "passive"))
    )
    (net (code "125") (name "unconnected-(USB1-TX1+-PadA2)") (class "Default")
      (node (ref "USB1") (pin "A2") (pinfunction "TX1+_A2") (pintype "passive"))
    )
    (net (code "126") (name "unconnected-(USB1-TX1--PadA3)") (class "Default")
      (node (ref "USB1") (pin "A3") (pinfunction "TX1-_A3") (pintype "passive"))
    )
    (net (code "127") (name "unconnected-(USB1-TX2+-PadB2)") (class "Default")
      (node (ref "USB1") (pin "B2") (pinfunction "TX2+_B2") (pintype "passive"))
    )
    (net (code "128") (name "unconnected-(USB1-TX2--PadB3)") (class "Default")
      (node (ref "USB1") (pin "B3") (pinfunction "TX2-_B3") (pintype "passive"))
    )
  )
)
